# SiLPA_HE_RF_channel.net
KiCad netlist of a schematic drawn in Altium Designer
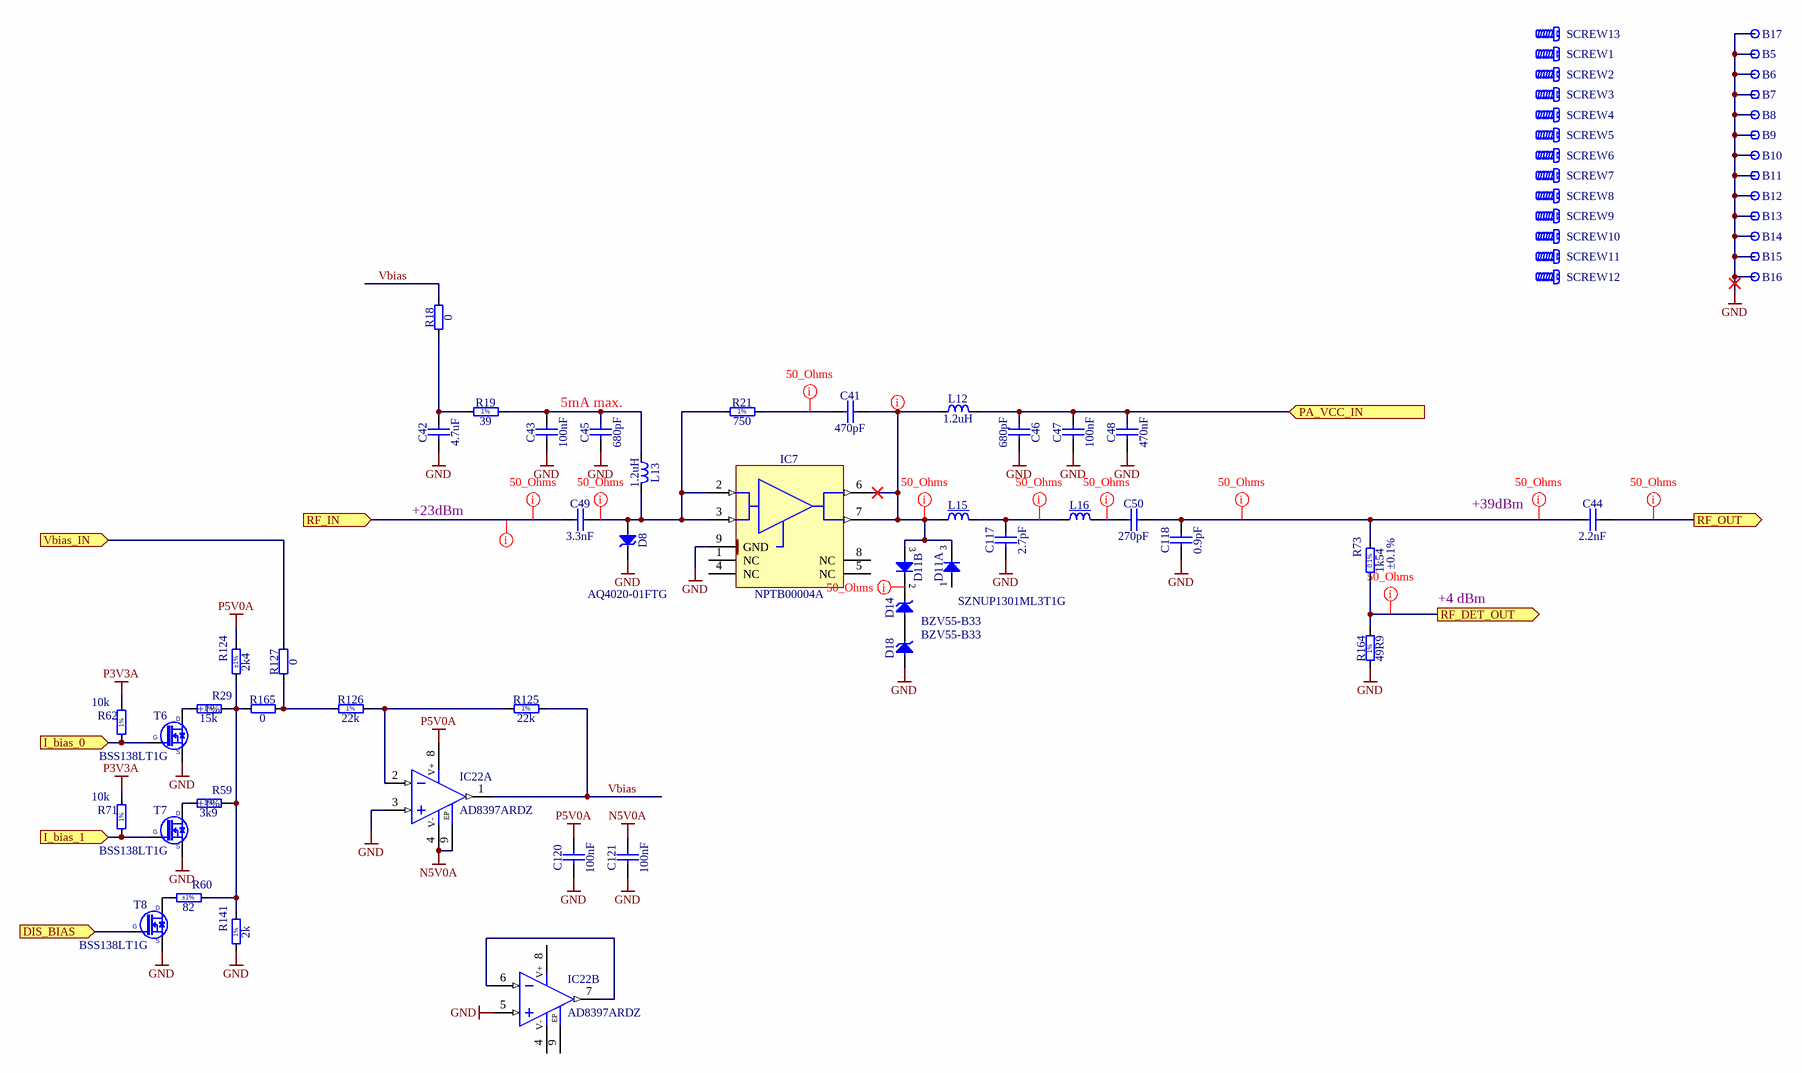
[diagram p0: SiLPA_HE_RF_channel.SchDoc]

(export (version "E")
  (design (tool "Eeschema 10.0.6"))
  (components
    (comp (ref "B5")
      (value "Plated Hole")
      (footprint "MTG240_400")
      (description "Single Terminal Socket")
      (fields (field (name "PART NUMBER") "PLATED_HOLE2.4_PAD4.0") (field (name "AUTHOR") "CERN DEM JMW"))
      (libsource (lib "SiLPA_own") (part "PLATED_HOLE2.4_PAD4.0"))
    )
    (comp (ref "B6")
      (value "Plated Hole")
      (footprint "MTG240_400")
      (description "Single Terminal Socket")
      (fields (field (name "PART NUMBER") "PLATED_HOLE2.4_PAD4.0") (field (name "AUTHOR") "CERN DEM JMW"))
      (libsource (lib "SiLPA_own") (part "PLATED_HOLE2.4_PAD4.0"))
    )
    (comp (ref "B7")
      (value "Plated Hole")
      (footprint "MTG240_400")
      (description "Single Terminal Socket")
      (fields (field (name "PART NUMBER") "PLATED_HOLE2.4_PAD4.0") (field (name "AUTHOR") "CERN DEM JMW"))
      (libsource (lib "SiLPA_own") (part "PLATED_HOLE2.4_PAD4.0"))
    )
    (comp (ref "B8")
      (value "Plated Hole")
      (footprint "MTG240_400")
      (description "Single Terminal Socket")
      (fields (field (name "PART NUMBER") "PLATED_HOLE2.4_PAD4.0") (field (name "AUTHOR") "CERN DEM JMW"))
      (libsource (lib "SiLPA_own") (part "PLATED_HOLE2.4_PAD4.0"))
    )
    (comp (ref "B9")
      (value "Plated Hole")
      (footprint "MTG240_400")
      (description "Single Terminal Socket")
      (fields (field (name "PART NUMBER") "PLATED_HOLE2.4_PAD4.0") (field (name "AUTHOR") "CERN DEM JMW"))
      (libsource (lib "SiLPA_own") (part "PLATED_HOLE2.4_PAD4.0"))
    )
    (comp (ref "B10")
      (value "Plated Hole")
      (footprint "MTG240_400")
      (description "Single Terminal Socket")
      (fields (field (name "PART NUMBER") "PLATED_HOLE2.4_PAD4.0") (field (name "AUTHOR") "CERN DEM JMW"))
      (libsource (lib "SiLPA_own") (part "PLATED_HOLE2.4_PAD4.0"))
    )
    (comp (ref "B11")
      (value "Plated Hole")
      (footprint "MTG240_400")
      (description "Single Terminal Socket")
      (fields (field (name "PART NUMBER") "PLATED_HOLE2.4_PAD4.0") (field (name "AUTHOR") "CERN DEM JMW"))
      (libsource (lib "SiLPA_own") (part "PLATED_HOLE2.4_PAD4.0"))
    )
    (comp (ref "B12")
      (value "Plated Hole")
      (footprint "MTG240_400")
      (description "Single Terminal Socket")
      (fields (field (name "PART NUMBER") "PLATED_HOLE2.4_PAD4.0") (field (name "AUTHOR") "CERN DEM JMW"))
      (libsource (lib "SiLPA_own") (part "PLATED_HOLE2.4_PAD4.0"))
    )
    (comp (ref "B13")
      (value "Plated Hole")
      (footprint "MTG240_400")
      (description "Single Terminal Socket")
      (fields (field (name "PART NUMBER") "PLATED_HOLE2.4_PAD4.0") (field (name "AUTHOR") "CERN DEM JMW"))
      (libsource (lib "SiLPA_own") (part "PLATED_HOLE2.4_PAD4.0"))
    )
    (comp (ref "B14")
      (value "Plated Hole")
      (footprint "MTG240_400")
      (description "Single Terminal Socket")
      (fields (field (name "PART NUMBER") "PLATED_HOLE2.4_PAD4.0") (field (name "AUTHOR") "CERN DEM JMW"))
      (libsource (lib "SiLPA_own") (part "PLATED_HOLE2.4_PAD4.0"))
    )
    (comp (ref "B15")
      (value "Plated Hole")
      (footprint "MTG240_400")
      (description "Single Terminal Socket")
      (fields (field (name "PART NUMBER") "PLATED_HOLE2.4_PAD4.0") (field (name "AUTHOR") "CERN DEM JMW"))
      (libsource (lib "SiLPA_own") (part "PLATED_HOLE2.4_PAD4.0"))
    )
    (comp (ref "B16")
      (value "Plated Hole")
      (footprint "MTG240_400")
      (description "Single Terminal Socket")
      (fields (field (name "PART NUMBER") "PLATED_HOLE2.4_PAD4.0") (field (name "AUTHOR") "CERN DEM JMW"))
      (libsource (lib "SiLPA_own") (part "PLATED_HOLE2.4_PAD4.0"))
    )
    (comp (ref "B17")
      (value "Plated Hole")
      (footprint "MTG240_400")
      (description "Single Terminal Socket")
      (fields (field (name "PART NUMBER") "PLATED_HOLE2.4_PAD4.0") (field (name "AUTHOR") "CERN DEM JMW"))
      (libsource (lib "SiLPA_own") (part "PLATED_HOLE2.4_PAD4.0"))
    )
    (comp (ref "C41")
      (value "470pF")
      (footprint "CAPC1608X87N")
      (description "Non-polarised capacitor")
      (fields
        (field (name "PART NUMBER") "CC0603_470PF_50V_1%_NP0")
        (field (name "VOLTAGE") "50V")
        (field (name "AUTHOR") "GK")
      )
      (libsource (lib "Passives_RC") (part "CC0603_470PF_50V_1%_NP0"))
    )
    (comp (ref "C42")
      (value "4.7uF")
      (footprint "CAPC1709X95N")
      (description "Non-polarised capacitor")
      (fields
        (field (name "MANUFACTURER") "GENERIC")
        (field (name "MANUFACTURER PART NUMBER") "CC0603_4.7UF_16V_10%_X5R")
        (field (name "AUTHOR") "CERN DEM JLC")
      )
      (libsource (lib "Capacitors") (part "Capacitor - non polarized"))
    )
    (comp (ref "C43")
      (value "100nF")
      (footprint "CAPC1005X55N")
      (description "Non-polarised capacitor")
      (fields
        (field (name "MANUFACTURER") "GENERIC")
        (field (name "MANUFACTURER PART NUMBER") "CC0402_100NF_50V_10%_X7R")
        (field (name "AUTHOR") "CERN DEM MR")
      )
      (libsource (lib "Capacitors") (part "Capacitor - non polarized"))
    )
    (comp (ref "C44")
      (value "2.2nF")
      (footprint "CAPC1608X87N")
      (description "Non-polarised capacitor")
      (fields
        (field (name "MANUFACTURER") "GENERIC")
        (field (name "MANUFACTURER PART NUMBER") "CC0603_2.2NF_50V_5%_C0G")
        (field (name "AUTHOR") "CERN DEM JMW")
      )
      (libsource (lib "Capacitors") (part "Capacitor - non polarized"))
    )
    (comp (ref "C45")
      (value "680pF")
      (footprint "CAPC1005X55N")
      (description "Non-polarised capacitor")
      (fields
        (field (name "MANUFACTURER") "GENERIC")
        (field (name "MANUFACTURER PART NUMBER") "CC0402_680PF_50V_10%_X7R")
        (field (name "AUTHOR") "CERN DEM JLC")
      )
      (libsource (lib "Capacitors") (part "Capacitor - non polarized"))
    )
    (comp (ref "C46")
      (value "680pF")
      (footprint "CAPC1608X87N")
      (description "Non-polarised capacitor")
      (fields
        (field (name "MANUFACTURER") "GENERIC")
        (field (name "MANUFACTURER PART NUMBER") "CC0603_680PF_50V_5%_NP0")
        (field (name "AUTHOR") "CERN DEM JLC")
      )
      (libsource (lib "Capacitors") (part "Capacitor - non polarized"))
    )
    (comp (ref "C47")
      (value "100nF")
      (footprint "CAPC1005X55N")
      (description "Non-polarised capacitor")
      (fields
        (field (name "MANUFACTURER") "GENERIC")
        (field (name "MANUFACTURER PART NUMBER") "CC0402_100NF_50V_10%_X7R")
        (field (name "AUTHOR") "CERN DEM MR")
      )
      (libsource (lib "Capacitors") (part "Capacitor - non polarized"))
    )
    (comp (ref "C48")
      (value "470nF")
      (footprint "CAPC2012X110N")
      (description "Non-polarised capacitor")
      (fields
        (field (name "PART NUMBER") "CC0805_470NF_50V_10%_X7R")
        (field (name "VOLTAGE") "50V")
        (field (name "AUTHOR") "CERN DEM JLC")
      )
      (libsource (lib "Capacitors") (part "Capacitor - non polarized"))
    )
    (comp (ref "C49")
      (value "3.3nF")
      (footprint "CAPC1608X87N")
      (description "Non-polarised capacitor")
      (fields
        (field (name "MANUFACTURER") "GENERIC")
        (field (name "MANUFACTURER PART NUMBER") "CC0603_3.3NF_50V_5%_C0G")
        (field (name "AUTHOR") "CERN DEM MR")
      )
      (libsource (lib "Capacitors") (part "Capacitor - non polarized"))
    )
    (comp (ref "C50")
      (value "270pF")
      (footprint "CAPC1608X87N")
      (description "Non-polarised capacitor")
      (fields
        (field (name "PART NUMBER") "CC0603_270PF_50V_1%_NP0")
        (field (name "VOLTAGE") "50V")
        (field (name "AUTHOR") "GK")
      )
      (libsource (lib "Passives_RC") (part "CC0603_270PF_50V_1%_NP0"))
    )
    (comp (ref "C117")
      (value "2.7pF")
      (footprint "CAPC1608X87N")
      (description "Non-polarised capacitor")
      (fields
        (field (name "PART NUMBER") "CC0603_2.7PF_50V_0.25PF_NP0")
        (field (name "VOLTAGE") "50V")
        (field (name "AUTHOR") "CERN DEM JLC")
      )
      (libsource (lib "Capacitors") (part "Capacitor - non polarized"))
    )
    (comp (ref "C118")
      (value "0.9pF")
      (footprint "CAPC1608X87N")
      (description "Non-polarised capacitor")
      (fields
        (field (name "PART NUMBER") "CC0603_0.9PF_50V_0.05PF_NP0")
        (field (name "VOLTAGE") "50V")
        (field (name "AUTHOR") "GK")
      )
      (libsource (lib "Passives_RC") (part "CC0603_0.9PF_50V_0.05PF_NP0"))
    )
    (comp (ref "C120")
      (value "100nF")
      (footprint "CAPC1005X55N")
      (description "Non-polarised capacitor")
      (fields
        (field (name "PART NUMBER") "CC0402_100NF_50V_10%_X7R")
        (field (name "VOLTAGE") "50V")
        (field (name "AUTHOR") "CERN DEM MR")
      )
      (libsource (lib "Capacitors") (part "Capacitor - non polarized"))
    )
    (comp (ref "C121")
      (value "100nF")
      (footprint "CAPC1005X55N")
      (description "Non-polarised capacitor")
      (fields
        (field (name "PART NUMBER") "CC0402_100NF_50V_10%_X7R")
        (field (name "VOLTAGE") "50V")
        (field (name "AUTHOR") "CERN DEM MR")
      )
      (libsource (lib "Capacitors") (part "Capacitor - non polarized"))
    )
    (comp (ref "D8")
      (value "AQ4020-01FTG")
      (footprint "SOD2512X110N")
      (description "4V Transient Voltage Suppressor Diode (Uni-Directional)")
      (fields (field (name "VOLTAGE") "4V") (field (name "POWER") "735W") (field (name "AUTHOR") "GK"))
      (libsource (lib "Diodes") (part "D_TVS_AQ4020-01FTG"))
    )
    (comp (ref "D11")
      (value "SZNUP1301ML3T1G")
      (footprint "SOT95P240X110-3N")
      (description "Low Capacitance Diode Array for ESD Protection in a Single Data Line")
      (fields (field (name "VOLTAGE") "70V") (field (name "POWER") "215mA") (field (name "AUTHOR") "GK"))
      (libsource (lib "Diodes") (part "D_TVS_SZNUP1301ML3T1G"))
    )
    (comp (ref "D14")
      (value "BZV55-B33")
      (footprint "DIOMELF3515N")
      (description "Zener Diode")
      (fields
        (field (name "VOLTAGE") "33V")
        (field (name "POWER") "500mW")
        (field (name "AUTHOR") "CERN DEM JLC")
      )
      (libsource (lib "ICs And Semiconductors") (part "Diode Zener"))
    )
    (comp (ref "D18")
      (value "BZV55-B33")
      (footprint "DIOMELF3515N")
      (description "Zener Diode")
      (fields
        (field (name "VOLTAGE") "33V")
        (field (name "POWER") "500mW")
        (field (name "AUTHOR") "CERN DEM JLC")
      )
      (libsource (lib "ICs And Semiconductors") (part "Diode Zener"))
    )
    (comp (ref "IC7")
      (value "NPTB00004A")
      (footprint "SOIC127P610X167-9N-R245X335")
      (description "GaN Wideband Transistor 28V, 5W, DC - 6GHz")
      (fields (field (name "MANUFACTURER") "MACOM") (field (name "AUTHOR") "CERN DEM BC"))
      (libsource (lib "ICs And Semiconductors") (part "NPTB00004A"))
    )
    (comp (ref "IC22")
      (value "AD8397ARDZ")
      (footprint "SOIC127P600X175-9N-R241X309")
      (description "Dual Operational Amplifier With Exposed Pad")
      (fields (field (name "MANUFACTURER") "ANALOG DEVICES") (field (name "AUTHOR") "CERN DEM JLC"))
      (libsource (lib "ICs And Semiconductors") (part "Operational Amplifier x2 Type1 EP"))
    )
    (comp (ref "L12")
      (value "1.2uH")
      (footprint "IND_TDK_ADL2012")
      (description "Inductor")
      (fields
        (field (name "PART NUMBER") "IND0805_TDK_ADL2012S-1R2M-T01")
        (field (name "POWER") "400mA")
        (field (name "AUTHOR") "GK")
      )
      (libsource (lib "Inductors_Transformers") (part "IND0805_TDK_ADL2012S-1R2M-T01"))
    )
    (comp (ref "L13")
      (value "1.2uH")
      (footprint "IND_TDK_ADL2012")
      (description "Inductor")
      (fields
        (field (name "PART NUMBER") "IND0805_TDK_ADL2012S-1R2M-T01")
        (field (name "POWER") "400mA")
        (field (name "AUTHOR") "GK")
      )
      (libsource (lib "") (part "IND0805_TDK_ADL2012S-1R2M-T01_1"))
    )
    (comp (ref "L15")
      (value "~")
      (footprint "IND_MURATA_LQW18AN_G8")
      (description "Inductor With Core")
      (fields
        (field (name "PART NUMBER") "IND0603_4.7NH_2%_MURATA_LQW18AN4N7G8Z")
        (field (name "POWER") "1.5A")
        (field (name "AUTHOR") "CERN DEM BC")
      )
      (libsource (lib "SiLPA_own") (part "Inductor With Magnetic core"))
    )
    (comp (ref "L16")
      (value "~")
      (footprint "IND_MURATA_LQW18AN_G8")
      (description "Inductor With Core")
      (fields
        (field (name "PART NUMBER") "IND0603_6.8NH_2%_MURATA_LQW18AN6N8G8Z")
        (field (name "POWER") "1.9A")
        (field (name "AUTHOR") "CERN DEM BC")
      )
      (libsource (lib "SiLPA_own") (part "IND0603_6.8NH_2%_MURATA_LQW18AN6N8G8Z"))
    )
    (comp (ref "R18")
      (value "0")
      (footprint "RESC1005X40N")
      (description "Resistor")
      (fields
        (field (name "MANUFACTURER") "GENERIC")
        (field (name "MANUFACTURER PART NUMBER") "R0402_0R_JUMPER")
        (field (name "AUTHOR") "CERN DEM JLC")
      )
      (libsource (lib "Resistors") (part "Resistor"))
    )
    (comp (ref "R19")
      (value "39")
      (footprint "RESC1005X40N")
      (description "Resistor - 1%")
      (fields
        (field (name "PART NUMBER") "R0402_39R_1%_0.0625W_100PPM")
        (field (name "POWER") "0.0625W")
        (field (name "AUTHOR") "CERN DEM JLC")
      )
      (libsource (lib "Resistors") (part "Resistor - 1%"))
    )
    (comp (ref "R21")
      (value "750")
      (footprint "RESC1608X55N")
      (description "Resistor - 1%")
      (fields
        (field (name "PART NUMBER") "R0603_750R_1%_0.1W_100PPM")
        (field (name "POWER") "0.1W")
        (field (name "AUTHOR") "CERN DEM JLC")
      )
      (libsource (lib "Resistors") (part "Resistor - 1%"))
    )
    (comp (ref "R29")
      (value "15k")
      (footprint "RESC1005X40N")
      (description "Resistor - 1%")
      (fields
        (field (name "TOLERANCE") "±1%")
        (field (name "PART NUMBER") "R0402_15K_1%_0.0625W_100PPM")
        (field (name "POWER") "0.0625W")
        (field (name "AUTHOR") "CERN DEM JMW")
      )
      (libsource (lib "Resistors") (part "Resistor - 1%"))
    )
    (comp (ref "R59")
      (value "3k9")
      (footprint "RESC1005X40N")
      (description "Resistor - 1%")
      (fields
        (field (name "TOLERANCE") "±1%")
        (field (name "PART NUMBER") "R0402_3K9_1%_0.0625W_100PPM")
        (field (name "POWER") "0.0625W")
        (field (name "AUTHOR") "CERN DEM JLC")
      )
      (libsource (lib "Resistors") (part "Resistor - 1%"))
    )
    (comp (ref "R60")
      (value "82")
      (footprint "RESC1005X40N")
      (description "Resistor - 1%")
      (fields
        (field (name "TOLERANCE") "±1%")
        (field (name "PART NUMBER") "R0402_82R_1%_0.0625W_100PPM")
        (field (name "POWER") "0.0625W")
        (field (name "AUTHOR") "CERN DEM JLC")
      )
      (libsource (lib "Resistors") (part "Resistor - 1%"))
    )
    (comp (ref "R62")
      (value "10k")
      (footprint "RESC1005X40N")
      (description "Resistor - 1%")
      (fields
        (field (name "PART NUMBER") "R0402_10K_1%_0.0625W_100PPM")
        (field (name "POWER") "0.0625W")
        (field (name "AUTHOR") "CERN DEM JLC")
      )
      (libsource (lib "Resistors") (part "Resistor - 1%"))
    )
    (comp (ref "R71")
      (value "10k")
      (footprint "RESC1005X40N")
      (description "Resistor - 1%")
      (fields
        (field (name "PART NUMBER") "R0402_10K_1%_0.0625W_100PPM")
        (field (name "POWER") "0.0625W")
        (field (name "AUTHOR") "CERN DEM JLC")
      )
      (libsource (lib "Resistors") (part "Resistor - 1%"))
    )
    (comp (ref "R73")
      (value "1k54")
      (footprint "RESC2012X60N")
      (description "Resistor - 0.1%")
      (fields
        (field (name "TOLERANCE") "±0.1%")
        (field (name "PART NUMBER") "R0805_1K54_0.1%_0.1W_10PPM")
        (field (name "POWER") "0.1W")
        (field (name "AUTHOR") "CERN DEM JLC")
      )
      (libsource (lib "Resistors") (part "Resistor - 0.1%"))
    )
    (comp (ref "R124")
      (value "2k4")
      (footprint "RESC1005X40N")
      (description "Resistor - 1%")
      (fields
        (field (name "TOLERANCE") "±1%")
        (field (name "PART NUMBER") "R0402_2K4_1%_0.0625W_100PPM")
        (field (name "POWER") "0.0625W")
        (field (name "AUTHOR") "CERN DEM JLC")
      )
      (libsource (lib "Resistors") (part "Resistor - 1%"))
    )
    (comp (ref "R125")
      (value "22k")
      (footprint "RESC1005X40N")
      (description "Resistor - 1%")
      (fields
        (field (name "PART NUMBER") "R0402_22K_1%_0.0625W_100PPM")
        (field (name "POWER") "0.0625W")
        (field (name "AUTHOR") "CERN DEM JLC")
      )
      (libsource (lib "Resistors") (part "Resistor - 1%"))
    )
    (comp (ref "R126")
      (value "22k")
      (footprint "RESC1005X40N")
      (description "Resistor - 1%")
      (fields
        (field (name "PART NUMBER") "R0402_22K_1%_0.0625W_100PPM")
        (field (name "POWER") "0.0625W")
        (field (name "AUTHOR") "CERN DEM JLC")
      )
      (libsource (lib "Resistors") (part "Resistor - 1%"))
    )
    (comp (ref "R127")
      (value "0")
      (footprint "RESC1005X40N")
      (description "Resistor")
      (fields
        (field (name "MANUFACTURER") "GENERIC")
        (field (name "MANUFACTURER PART NUMBER") "R0402_0R_JUMPER")
        (field (name "AUTHOR") "CERN DEM JLC")
      )
      (libsource (lib "Resistors") (part "Resistor"))
    )
    (comp (ref "R141")
      (value "2k")
      (footprint "RESC1005X40N")
      (description "Resistor - 1%")
      (fields
        (field (name "TOLERANCE") "±1%")
        (field (name "PART NUMBER") "R0402_2K_1%_0.0625W_100PPM")
        (field (name "AUTHOR") "CERN DEM JLC")
      )
      (libsource (lib "Resistors") (part "Resistor - 1%"))
    )
    (comp (ref "R164")
      (value "49R9")
      (footprint "RESC1608X55N")
      (description "Resistor - 1%")
      (fields
        (field (name "PART NUMBER") "R0603_49K9_1%_0.1W_100PPM")
        (field (name "POWER") "0.1W")
        (field (name "AUTHOR") "CERN DEM JLC")
      )
      (libsource (lib "Resistors") (part "Resistor - 1%"))
    )
    (comp (ref "R165")
      (value "0")
      (footprint "RESC1005X40N")
      (description "Resistor")
      (fields
        (field (name "MANUFACTURER") "GENERIC")
        (field (name "MANUFACTURER PART NUMBER") "R0402_0R_JUMPER")
        (field (name "AUTHOR") "CERN DEM JLC")
      )
      (libsource (lib "Resistors") (part "Resistor"))
    )
    (comp (ref "SCREW1")
      (value "~")
      (footprint "BOSSARD_BN5687-3061579_v")
      (description "Screw")
      (fields
        (field (name "PART NUMBER") "BOSSARD_BN5687-3061579_v")
        (field (name "MANUFACTURER") "BOSSARD")
        (field (name "AUTHOR") "CERN DEM JLC")
      )
      (libsource (lib "SiLPA_own") (part "Screw"))
    )
    (comp (ref "SCREW2")
      (value "~")
      (footprint "BOSSARD_BN5687-3061579_v")
      (description "Screw")
      (fields
        (field (name "PART NUMBER") "BOSSARD_BN5687-3061579_v")
        (field (name "MANUFACTURER") "BOSSARD")
        (field (name "AUTHOR") "CERN DEM JLC")
      )
      (libsource (lib "SiLPA_own") (part "Screw"))
    )
    (comp (ref "SCREW3")
      (value "~")
      (footprint "BOSSARD_BN5687-3061579_v")
      (description "Screw")
      (fields
        (field (name "PART NUMBER") "BOSSARD_BN5687-3061579_v")
        (field (name "MANUFACTURER") "BOSSARD")
        (field (name "AUTHOR") "CERN DEM JLC")
      )
      (libsource (lib "SiLPA_own") (part "Screw"))
    )
    (comp (ref "SCREW4")
      (value "~")
      (footprint "BOSSARD_BN5687-3061579_v")
      (description "Screw")
      (fields
        (field (name "PART NUMBER") "BOSSARD_BN5687-3061579_v")
        (field (name "MANUFACTURER") "BOSSARD")
        (field (name "AUTHOR") "CERN DEM JLC")
      )
      (libsource (lib "SiLPA_own") (part "Screw"))
    )
    (comp (ref "SCREW5")
      (value "~")
      (footprint "BOSSARD_BN5687-3061579_v")
      (description "Screw")
      (fields
        (field (name "PART NUMBER") "BOSSARD_BN5687-3061579_v")
        (field (name "MANUFACTURER") "BOSSARD")
        (field (name "AUTHOR") "CERN DEM JLC")
      )
      (libsource (lib "SiLPA_own") (part "Screw"))
    )
    (comp (ref "SCREW6")
      (value "~")
      (footprint "BOSSARD_BN5687-3061579_v")
      (description "Screw")
      (fields
        (field (name "PART NUMBER") "BOSSARD_BN5687-3061579_v")
        (field (name "MANUFACTURER") "BOSSARD")
        (field (name "AUTHOR") "CERN DEM JLC")
      )
      (libsource (lib "SiLPA_own") (part "Screw"))
    )
    (comp (ref "SCREW7")
      (value "~")
      (footprint "BOSSARD_BN5687-3061579_v")
      (description "Screw")
      (fields
        (field (name "PART NUMBER") "BOSSARD_BN5687-3061579_v")
        (field (name "MANUFACTURER") "BOSSARD")
        (field (name "AUTHOR") "CERN DEM JLC")
      )
      (libsource (lib "SiLPA_own") (part "Screw"))
    )
    (comp (ref "SCREW8")
      (value "~")
      (footprint "BOSSARD_BN5687-3061579_v")
      (description "Screw")
      (fields
        (field (name "PART NUMBER") "BOSSARD_BN5687-3061579_v")
        (field (name "MANUFACTURER") "BOSSARD")
        (field (name "AUTHOR") "CERN DEM JLC")
      )
      (libsource (lib "SiLPA_own") (part "Screw"))
    )
    (comp (ref "SCREW9")
      (value "~")
      (footprint "BOSSARD_BN5687-3061579_v")
      (description "Screw")
      (fields
        (field (name "PART NUMBER") "BOSSARD_BN5687-3061579_v")
        (field (name "MANUFACTURER") "BOSSARD")
        (field (name "AUTHOR") "CERN DEM JLC")
      )
      (libsource (lib "SiLPA_own") (part "Screw"))
    )
    (comp (ref "SCREW10")
      (value "~")
      (footprint "BOSSARD_BN5687-3061579_v")
      (description "Screw")
      (fields
        (field (name "PART NUMBER") "BOSSARD_BN5687-3061579_v")
        (field (name "MANUFACTURER") "BOSSARD")
        (field (name "AUTHOR") "CERN DEM JLC")
      )
      (libsource (lib "SiLPA_own") (part "Screw"))
    )
    (comp (ref "SCREW11")
      (value "~")
      (footprint "BOSSARD_BN5687-3061579_v")
      (description "Screw")
      (fields
        (field (name "PART NUMBER") "BOSSARD_BN5687-3061579_v")
        (field (name "MANUFACTURER") "BOSSARD")
        (field (name "AUTHOR") "CERN DEM JLC")
      )
      (libsource (lib "SiLPA_own") (part "Screw"))
    )
    (comp (ref "SCREW12")
      (value "~")
      (footprint "BOSSARD_BN5687-3061579_v")
      (description "Screw")
      (fields
        (field (name "PART NUMBER") "BOSSARD_BN5687-3061579_v")
        (field (name "MANUFACTURER") "BOSSARD")
        (field (name "AUTHOR") "CERN DEM JLC")
      )
      (libsource (lib "SiLPA_own") (part "Screw"))
    )
    (comp (ref "SCREW13")
      (value "~")
      (footprint "BOSSARD_BN5687-3061579_v")
      (description "Screw")
      (fields
        (field (name "PART NUMBER") "BOSSARD_BN5687-3061579_v")
        (field (name "MANUFACTURER") "BOSSARD")
        (field (name "AUTHOR") "CERN DEM JLC")
      )
      (libsource (lib "SiLPA_own") (part "Screw"))
    )
    (comp (ref "T6")
      (value "BSS138LT1G")
      (footprint "SOT95P240X110-3N")
      (description "N-CHANNEL MOSFET WITH DIODE")
      (fields (field (name "MANUFACTURER") "ON SEMICONDUCTOR") (field (name "AUTHOR") "CERN DEM JLC"))
      (libsource (lib "ICs And Semiconductors") (part "N-MOSFET-D 1G 2S 3D"))
    )
    (comp (ref "T7")
      (value "BSS138LT1G")
      (footprint "SOT95P240X110-3N")
      (description "N-CHANNEL MOSFET WITH DIODE")
      (fields (field (name "MANUFACTURER") "ON SEMICONDUCTOR") (field (name "AUTHOR") "CERN DEM JLC"))
      (libsource (lib "ICs And Semiconductors") (part "N-MOSFET-D 1G 2S 3D"))
    )
    (comp (ref "T8")
      (value "BSS138LT1G")
      (footprint "SOT95P240X110-3N")
      (description "N-CHANNEL MOSFET WITH DIODE")
      (fields (field (name "MANUFACTURER") "ON SEMICONDUCTOR") (field (name "AUTHOR") "CERN DEM JLC"))
      (libsource (lib "ICs And Semiconductors") (part "N-MOSFET-D 1G 2S 3D"))
    )
  )
  (nets
    (net (code "1") (name "/DIS_BIAS") (class "Default")
      (node (ref "T8") (pin "1") (pinfunction "G_1") (pintype "passive"))
    )
    (net (code "2") (name "/I_bias_0") (class "Default")
      (node (ref "R62") (pin "1") (pinfunction "1_1") (pintype "passive"))
      (node (ref "T6") (pin "1") (pinfunction "G_1") (pintype "passive"))
    )
    (net (code "3") (name "/I_bias_1") (class "Default")
      (node (ref "R71") (pin "1") (pinfunction "1_1") (pintype "passive"))
      (node (ref "T7") (pin "1") (pinfunction "G_1") (pintype "passive"))
    )
    (net (code "4") (name "/PA_VCC_IN") (class "Default")
      (node (ref "C46") (pin "2") (pinfunction "2_2") (pintype "passive"))
      (node (ref "C47") (pin "2") (pinfunction "2_2") (pintype "passive"))
      (node (ref "C48") (pin "2") (pinfunction "2_2") (pintype "passive"))
      (node (ref "L12") (pin "2") (pinfunction "2_2") (pintype "passive"))
    )
    (net (code "5") (name "/RF_DET_OUT") (class "Default")
      (node (ref "R164") (pin "2") (pinfunction "2_2") (pintype "passive"))
      (node (ref "R73") (pin "1") (pinfunction "1_1") (pintype "passive"))
    )
    (net (code "6") (name "/RF_IN") (class "Default")
      (node (ref "C49") (pin "2") (pinfunction "2_2") (pintype "passive"))
    )
    (net (code "7") (name "/RF_OUT") (class "Default")
      (node (ref "C44") (pin "2") (pinfunction "2_2") (pintype "passive"))
    )
    (net (code "8") (name "/Vbias") (class "Default")
      (node (ref "IC22") (pin "1") (pinfunction "OUT_1") (pintype "output"))
      (node (ref "R125") (pin "1") (pinfunction "1_1") (pintype "passive"))
      (node (ref "R18") (pin "2") (pinfunction "2_2") (pintype "passive"))
    )
    (net (code "9") (name "/Vbias_IN") (class "Default")
      (node (ref "R127") (pin "2") (pinfunction "2_2") (pintype "passive"))
    )
    (net (code "10") (name "GND") (class "Default")
      (node (ref "B10") (pin "1") (pinfunction "1_1") (pintype "bidirectional"))
      (node (ref "B11") (pin "1") (pinfunction "1_1") (pintype "bidirectional"))
      (node (ref "B12") (pin "1") (pinfunction "1_1") (pintype "bidirectional"))
      (node (ref "B13") (pin "1") (pinfunction "1_1") (pintype "bidirectional"))
      (node (ref "B14") (pin "1") (pinfunction "1_1") (pintype "bidirectional"))
      (node (ref "B15") (pin "1") (pinfunction "1_1") (pintype "bidirectional"))
      (node (ref "B16") (pin "1") (pinfunction "1_1") (pintype "bidirectional"))
      (node (ref "B17") (pin "1") (pinfunction "1_1") (pintype "bidirectional"))
      (node (ref "B5") (pin "1") (pinfunction "1_1") (pintype "bidirectional"))
      (node (ref "B6") (pin "1") (pinfunction "1_1") (pintype "bidirectional"))
      (node (ref "B7") (pin "1") (pinfunction "1_1") (pintype "bidirectional"))
      (node (ref "B8") (pin "1") (pinfunction "1_1") (pintype "bidirectional"))
      (node (ref "B9") (pin "1") (pinfunction "1_1") (pintype "bidirectional"))
      (node (ref "C117") (pin "1") (pinfunction "1_1") (pintype "passive"))
      (node (ref "C118") (pin "1") (pinfunction "1_1") (pintype "passive"))
      (node (ref "C120") (pin "1") (pinfunction "1_1") (pintype "passive"))
      (node (ref "C121") (pin "1") (pinfunction "1_1") (pintype "passive"))
      (node (ref "C42") (pin "1") (pinfunction "1_1") (pintype "passive"))
      (node (ref "C43") (pin "1") (pinfunction "1_1") (pintype "passive"))
      (node (ref "C45") (pin "1") (pinfunction "1_1") (pintype "passive"))
      (node (ref "C46") (pin "1") (pinfunction "1_1") (pintype "passive"))
      (node (ref "C47") (pin "1") (pinfunction "1_1") (pintype "passive"))
      (node (ref "C48") (pin "1") (pinfunction "1_1") (pintype "passive"))
      (node (ref "D18") (pin "2") (pinfunction "A_2") (pintype "passive"))
      (node (ref "D8") (pin "1") (pinfunction "C_1") (pintype "passive"))
      (node (ref "IC22") (pin "3") (pinfunction "IN+_3") (pintype "input"))
      (node (ref "IC22") (pin "5") (pinfunction "IN+_5") (pintype "input"))
      (node (ref "IC7") (pin "9") (pinfunction "GND_9") (pintype "power_in"))
      (node (ref "R141") (pin "1") (pinfunction "1_1") (pintype "passive"))
      (node (ref "R164") (pin "1") (pinfunction "1_1") (pintype "passive"))
      (node (ref "T6") (pin "2") (pinfunction "S_2") (pintype "passive"))
      (node (ref "T7") (pin "2") (pinfunction "S_2") (pintype "passive"))
      (node (ref "T8") (pin "2") (pinfunction "S_2") (pintype "passive"))
    )
    (net (code "11") (name "N5V0A") (class "Default")
      (node (ref "C121") (pin "2") (pinfunction "2_2") (pintype "passive"))
      (node (ref "IC22") (pin "4") (pinfunction "V-_4") (pintype "power_in"))
      (node (ref "IC22") (pin "9") (pinfunction "Exposed_Pad_9") (pintype "power_in"))
    )
    (net (code "12") (name "Net-(C41-Pad1)") (class "Default")
      (node (ref "C41") (pin "1") (pinfunction "1_1") (pintype "passive"))
      (node (ref "R21") (pin "2") (pinfunction "2_2") (pintype "passive"))
    )
    (net (code "13") (name "Net-(C42-Pad2)") (class "Default")
      (node (ref "C42") (pin "2") (pinfunction "2_2") (pintype "passive"))
      (node (ref "R18") (pin "1") (pinfunction "1_1") (pintype "passive"))
      (node (ref "R19") (pin "1") (pinfunction "1_1") (pintype "passive"))
    )
    (net (code "14") (name "Net-(C43-Pad2)") (class "Default")
      (node (ref "C43") (pin "2") (pinfunction "2_2") (pintype "passive"))
      (node (ref "C45") (pin "2") (pinfunction "2_2") (pintype "passive"))
      (node (ref "L13") (pin "1") (pinfunction "1_1") (pintype "passive"))
      (node (ref "R19") (pin "2") (pinfunction "2_2") (pintype "passive"))
    )
    (net (code "15") (name "Net-(C50-Pad1)") (class "Default")
      (node (ref "C50") (pin "1") (pinfunction "1_1") (pintype "passive"))
      (node (ref "L16") (pin "2") (pinfunction "2_2") (pintype "passive"))
    )
    (net (code "16") (name "Net-(C117-Pad2)") (class "Default")
      (node (ref "C117") (pin "2") (pinfunction "2_2") (pintype "passive"))
      (node (ref "L15") (pin "2") (pinfunction "2_2") (pintype "passive"))
      (node (ref "L16") (pin "1") (pinfunction "1_1") (pintype "passive"))
    )
    (net (code "17") (name "Net-(C118-Pad2)") (class "Default")
      (node (ref "C118") (pin "2") (pinfunction "2_2") (pintype "passive"))
      (node (ref "C44") (pin "1") (pinfunction "1_1") (pintype "passive"))
      (node (ref "C50") (pin "2") (pinfunction "2_2") (pintype "passive"))
      (node (ref "R73") (pin "2") (pinfunction "2_2") (pintype "passive"))
    )
    (net (code "18") (name "Net-(D8-A)") (class "Default")
      (node (ref "C49") (pin "1") (pinfunction "1_1") (pintype "passive"))
      (node (ref "D8") (pin "2") (pinfunction "A_2") (pintype "passive"))
      (node (ref "IC7") (pin "2") (pinfunction "RF_IN_2") (pintype "input"))
      (node (ref "IC7") (pin "3") (pinfunction "RF_IN_3") (pintype "input"))
      (node (ref "L13") (pin "2") (pinfunction "2_2") (pintype "passive"))
      (node (ref "R21") (pin "1") (pinfunction "1_1") (pintype "passive"))
    )
    (net (code "19") (name "Net-(D11A-COMAC)") (class "Default")
      (node (ref "C41") (pin "2") (pinfunction "2_2") (pintype "passive"))
      (node (ref "D11") (pin "3") (pinfunction "COMAC_3") (pintype "passive"))
      (node (ref "IC7") (pin "6") (pinfunction "RF_OUT_6") (pintype "output"))
      (node (ref "IC7") (pin "7") (pinfunction "RF_OUT_7") (pintype "output"))
      (node (ref "L12") (pin "1") (pinfunction "1_1") (pintype "passive"))
      (node (ref "L15") (pin "1") (pinfunction "1_1") (pintype "passive"))
    )
    (net (code "20") (name "Net-(D11B-C)") (class "Default")
      (node (ref "D11") (pin "2") (pinfunction "C_2") (pintype "passive"))
      (node (ref "D14") (pin "1") (pinfunction "C_1") (pintype "passive"))
    )
    (net (code "21") (name "Net-(D14-A)") (class "Default")
      (node (ref "D14") (pin "2") (pinfunction "A_2") (pintype "passive"))
      (node (ref "D18") (pin "1") (pinfunction "C_1") (pintype "passive"))
    )
    (net (code "22") (name "Net-(IC22A-IN-)") (class "Default")
      (node (ref "IC22") (pin "2") (pinfunction "IN-_2") (pintype "input"))
      (node (ref "R125") (pin "2") (pinfunction "2_2") (pintype "passive"))
      (node (ref "R126") (pin "1") (pinfunction "1_1") (pintype "passive"))
    )
    (net (code "23") (name "Net-(IC22B-IN-)") (class "Default")
      (node (ref "IC22") (pin "6") (pinfunction "IN-_6") (pintype "input"))
      (node (ref "IC22") (pin "7") (pinfunction "OUT_7") (pintype "output"))
    )
    (net (code "24") (name "Net-(R124-Pad1)") (class "Default")
      (node (ref "R124") (pin "1") (pinfunction "1_1") (pintype "passive"))
      (node (ref "R141") (pin "2") (pinfunction "2_2") (pintype "passive"))
      (node (ref "R165") (pin "1") (pinfunction "1_1") (pintype "passive"))
      (node (ref "R29") (pin "2") (pinfunction "2_2") (pintype "passive"))
      (node (ref "R59") (pin "2") (pinfunction "2_2") (pintype "passive"))
      (node (ref "R60") (pin "2") (pinfunction "2_2") (pintype "passive"))
    )
    (net (code "25") (name "Net-(R126-Pad2)") (class "Default")
      (node (ref "R126") (pin "2") (pinfunction "2_2") (pintype "passive"))
      (node (ref "R127") (pin "1") (pinfunction "1_1") (pintype "passive"))
      (node (ref "R165") (pin "2") (pinfunction "2_2") (pintype "passive"))
    )
    (net (code "26") (name "Net-(T6-D)") (class "Default")
      (node (ref "R29") (pin "1") (pinfunction "1_1") (pintype "passive"))
      (node (ref "T6") (pin "3") (pinfunction "D_3") (pintype "passive"))
    )
    (net (code "27") (name "Net-(T7-D)") (class "Default")
      (node (ref "R59") (pin "1") (pinfunction "1_1") (pintype "passive"))
      (node (ref "T7") (pin "3") (pinfunction "D_3") (pintype "passive"))
    )
    (net (code "28") (name "Net-(T8-D)") (class "Default")
      (node (ref "R60") (pin "1") (pinfunction "1_1") (pintype "passive"))
      (node (ref "T8") (pin "3") (pinfunction "D_3") (pintype "passive"))
    )
    (net (code "29") (name "P3V3A") (class "Default")
      (node (ref "R62") (pin "2") (pinfunction "2_2") (pintype "passive"))
      (node (ref "R71") (pin "2") (pinfunction "2_2") (pintype "passive"))
    )
    (net (code "30") (name "P5V0A") (class "Default")
      (node (ref "C120") (pin "2") (pinfunction "2_2") (pintype "passive"))
      (node (ref "IC22") (pin "8") (pinfunction "V+_8") (pintype "power_in"))
      (node (ref "R124") (pin "2") (pinfunction "2_2") (pintype "passive"))
    )
    (net (code "31") (name "unconnected-(D11A-A-Pad1)") (class "Default")
      (node (ref "D11") (pin "1") (pinfunction "A_1") (pintype "passive"))
    )
    (net (code "32") (name "unconnected-(IC7-NC-Pad1)") (class "Default")
      (node (ref "IC7") (pin "1") (pinfunction "NC_1") (pintype "passive"))
    )
    (net (code "33") (name "unconnected-(IC7-NC-Pad4)") (class "Default")
      (node (ref "IC7") (pin "4") (pinfunction "NC_4") (pintype "passive"))
    )
    (net (code "34") (name "unconnected-(IC7-NC-Pad5)") (class "Default")
      (node (ref "IC7") (pin "5") (pinfunction "NC_5") (pintype "power_in"))
    )
    (net (code "35") (name "unconnected-(IC7-NC-Pad8)") (class "Default")
      (node (ref "IC7") (pin "8") (pinfunction "NC_8") (pintype "power_in"))
    )
    (net (code "36") (name "unconnected-(IC22B-Exposed_Pad-Pad9)") (class "Default")
      (node (ref "IC22") (pin "9") (pinfunction "Exposed_Pad_9") (pintype "power_in"))
    )
    (net (code "37") (name "unconnected-(IC22B-V+-Pad8)") (class "Default")
      (node (ref "IC22") (pin "8") (pinfunction "V+_8") (pintype "power_in"))
    )
    (net (code "38") (name "unconnected-(IC22B-V--Pad4)") (class "Default")
      (node (ref "IC22") (pin "4") (pinfunction "V-_4") (pintype "power_in"))
    )
  )
)
